# Arduinoboy_1.net
KiCad netlist of a schematic drawn in EAGLE
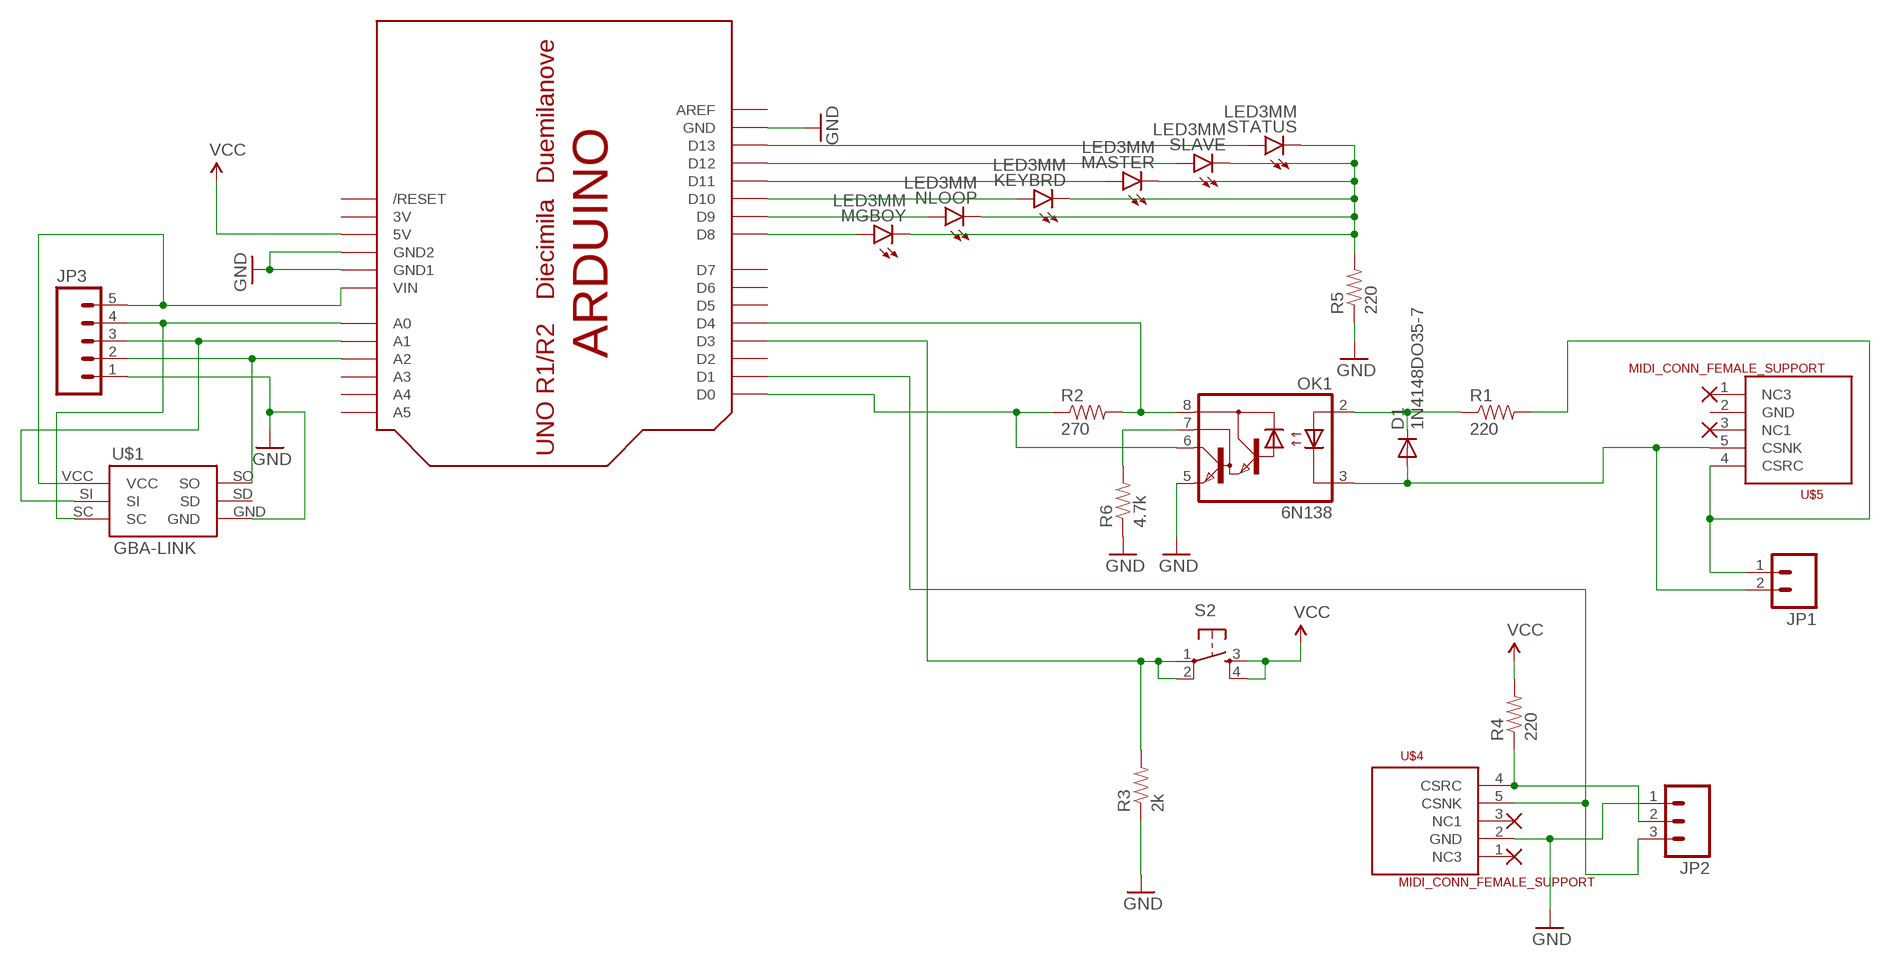
[diagram p0: schematic, sheet 1]

(export (version "E")
  (design (tool "Eeschema 10.0.6"))
  (components
    (comp (ref "D1")
      (value "1N4148DO35-7")
      (footprint "eagle-import:DO35-7")
      (libsource (lib "eagle-import") (part "1N4148DO35-7"))
    )
    (comp (ref "JP1")
      (value "M025MM")
      (footprint "eagle-import:SCREWTERMINAL-5MM-2")
      (libsource (lib "eagle-import") (part "M025MM"))
    )
    (comp (ref "JP2")
      (value "M03-SCREW-5MM")
      (footprint "eagle-import:SCREWTERMINAL-5MM-3")
      (libsource (lib "eagle-import") (part "M03-SCREW-5MM"))
    )
    (comp (ref "JP3")
      (value "M05SCREW")
      (footprint "eagle-import:SCREWTERMINAL-3.5MM-5")
      (libsource (lib "eagle-import") (part "M05SCREW"))
    )
    (comp (ref "KEYBRD")
      (value "LED3MM")
      (footprint "eagle-import:LED3MM")
      (libsource (lib "eagle-import") (part "LED3MM"))
    )
    (comp (ref "MASTER")
      (value "LED3MM")
      (footprint "eagle-import:LED3MM")
      (libsource (lib "eagle-import") (part "LED3MM"))
    )
    (comp (ref "MGBOY")
      (value "LED3MM")
      (footprint "eagle-import:LED3MM")
      (libsource (lib "eagle-import") (part "LED3MM"))
    )
    (comp (ref "NLOOP")
      (value "LED3MM")
      (footprint "eagle-import:LED3MM")
      (libsource (lib "eagle-import") (part "LED3MM"))
    )
    (comp (ref "OK1")
      (value "6N138")
      (footprint "eagle-import:DIL08")
      (libsource (lib "eagle-import") (part "6N138"))
    )
    (comp (ref "R1")
      (value "220")
      (footprint "eagle-import:AXIAL-0.3")
      (libsource (lib "eagle-import") (part "RESISTORAXIAL-0.3"))
    )
    (comp (ref "R2")
      (value "270")
      (footprint "eagle-import:AXIAL-0.3")
      (libsource (lib "eagle-import") (part "RESISTORAXIAL-0.3"))
    )
    (comp (ref "R3")
      (value "2k")
      (footprint "eagle-import:AXIAL-0.3")
      (libsource (lib "eagle-import") (part "RESISTORAXIAL-0.3"))
    )
    (comp (ref "R4")
      (value "220")
      (footprint "eagle-import:AXIAL-0.3")
      (libsource (lib "eagle-import") (part "RESISTORAXIAL-0.3"))
    )
    (comp (ref "R5")
      (value "220")
      (footprint "eagle-import:AXIAL-0.3")
      (libsource (lib "eagle-import") (part "RESISTORAXIAL-0.3"))
    )
    (comp (ref "R6")
      (value "4.7k")
      (footprint "eagle-import:AXIAL-0.3")
      (libsource (lib "eagle-import") (part "RESISTORAXIAL-0.3"))
    )
    (comp (ref "S2")
      (value "TAC_SWITCHPTH")
      (footprint "eagle-import:TACTILE-PTH")
      (libsource (lib "eagle-import") (part "TAC_SWITCHPTH"))
    )
    (comp (ref "SLAVE")
      (value "LED3MM")
      (footprint "eagle-import:LED3MM")
      (libsource (lib "eagle-import") (part "LED3MM"))
    )
    (comp (ref "STATUS")
      (value "LED3MM")
      (footprint "eagle-import:LED3MM")
      (libsource (lib "eagle-import") (part "LED3MM"))
    )
    (comp (ref "U$1")
      (value "GBA-LINK")
      (footprint "eagle-import:GBA-LINK")
      (libsource (lib "eagle-import") (part "GBA-LINK"))
    )
    (comp (ref "U$3")
      (value "ARDUINOUNO")
      (footprint "eagle-import:ARDUINO")
      (libsource (lib "eagle-import") (part "ARDUINOUNO"))
    )
    (comp (ref "U$4")
      (value "MIDI_CONN_FEMALE_SUPPORT")
      (footprint "eagle-import:DIN_5_FEMALE_SUPPORT")
      (libsource (lib "eagle-import") (part "MIDI_CONN_FEMALE_SUPPORT"))
    )
    (comp (ref "U$5")
      (value "MIDI_CONN_FEMALE_SUPPORT")
      (footprint "eagle-import:DIN_5_FEMALE_SUPPORT")
      (libsource (lib "eagle-import") (part "MIDI_CONN_FEMALE_SUPPORT"))
    )
  )
  (nets
    (net (code "1") (name "/3V") (class "Default")
      (node (ref "U$3") (pin "3V") (pinfunction "3V_3V") (pintype "power_in"))
    )
    (net (code "2") (name "GND") (class "Default")
      (node (ref "JP2") (pin "1") (pinfunction "1_1") (pintype "passive"))
      (node (ref "JP3") (pin "1") (pinfunction "1_1") (pintype "passive"))
      (node (ref "OK1") (pin "5") (pinfunction "GND_5") (pintype "passive"))
      (node (ref "R3") (pin "P$1") (pinfunction "1_P$1") (pintype "passive"))
      (node (ref "R5") (pin "P$1") (pinfunction "1_P$1") (pintype "passive"))
      (node (ref "R6") (pin "P$1") (pinfunction "1_P$1") (pintype "passive"))
      (node (ref "U$1") (pin "GND") (pinfunction "GND_GND") (pintype "bidirectional"))
      (node (ref "U$3") (pin "GND") (pinfunction "GND_GND") (pintype "power_in"))
      (node (ref "U$3") (pin "GND1") (pinfunction "GND1_GND1") (pintype "power_in"))
      (node (ref "U$3") (pin "GND2") (pinfunction "GND2_GND2") (pintype "power_in"))
      (node (ref "U$4") (pin "2") (pinfunction "GND_2") (pintype "bidirectional"))
    )
    (net (code "3") (name "Net-(JP3-Pad2)") (class "Default")
      (node (ref "JP3") (pin "2") (pinfunction "2_2") (pintype "passive"))
      (node (ref "U$1") (pin "SO") (pinfunction "SO_SO") (pintype "bidirectional"))
      (node (ref "U$3") (pin "A2") (pinfunction "A2_A2") (pintype "bidirectional"))
    )
    (net (code "4") (name "Net-(JP3-Pad3)") (class "Default")
      (node (ref "JP3") (pin "3") (pinfunction "3_3") (pintype "passive"))
      (node (ref "U$1") (pin "SI") (pinfunction "SI_SI") (pintype "bidirectional"))
      (node (ref "U$3") (pin "A1") (pinfunction "A1_A1") (pintype "bidirectional"))
    )
    (net (code "5") (name "Net-(JP3-Pad4)") (class "Default")
      (node (ref "JP3") (pin "4") (pinfunction "4_4") (pintype "passive"))
      (node (ref "U$1") (pin "SC") (pinfunction "SC_SC") (pintype "bidirectional"))
      (node (ref "U$3") (pin "A0") (pinfunction "A0_A0") (pintype "bidirectional"))
    )
    (net (code "6") (name "Net-(JP3-Pad5)") (class "Default")
      (node (ref "JP3") (pin "5") (pinfunction "5_5") (pintype "passive"))
      (node (ref "U$1") (pin "VCC") (pinfunction "VCC_VCC") (pintype "bidirectional"))
      (node (ref "U$3") (pin "VIN") (pinfunction "VIN_VIN") (pintype "power_in"))
    )
    (net (code "7") (name "Net-(KEYBRD-C)") (class "Default")
      (node (ref "KEYBRD") (pin "K") (pinfunction "C_K") (pintype "passive"))
      (node (ref "MASTER") (pin "K") (pinfunction "C_K") (pintype "passive"))
      (node (ref "MGBOY") (pin "K") (pinfunction "C_K") (pintype "passive"))
      (node (ref "NLOOP") (pin "K") (pinfunction "C_K") (pintype "passive"))
      (node (ref "R5") (pin "P$2") (pinfunction "2_P$2") (pintype "passive"))
      (node (ref "SLAVE") (pin "K") (pinfunction "C_K") (pintype "passive"))
      (node (ref "STATUS") (pin "K") (pinfunction "C_K") (pintype "passive"))
    )
    (net (code "8") (name "Net-(KEYBRD-PadA)") (class "Default")
      (node (ref "KEYBRD") (pin "A") (pinfunction "A_A") (pintype "passive"))
      (node (ref "U$3") (pin "D10") (pinfunction "D10_D10") (pintype "bidirectional"))
    )
    (net (code "9") (name "Net-(MASTER-PadA)") (class "Default")
      (node (ref "MASTER") (pin "A") (pinfunction "A_A") (pintype "passive"))
      (node (ref "U$3") (pin "D11") (pinfunction "D11_D11") (pintype "bidirectional"))
    )
    (net (code "10") (name "Net-(MGBOY-PadA)") (class "Default")
      (node (ref "MGBOY") (pin "A") (pinfunction "A_A") (pintype "passive"))
      (node (ref "U$3") (pin "D8") (pinfunction "D8_D8") (pintype "bidirectional"))
    )
    (net (code "11") (name "Net-(NLOOP-PadA)") (class "Default")
      (node (ref "NLOOP") (pin "A") (pinfunction "A_A") (pintype "passive"))
      (node (ref "U$3") (pin "D9") (pinfunction "D9_D9") (pintype "bidirectional"))
    )
    (net (code "12") (name "Net-(OK1-A)") (class "Default")
      (node (ref "D1") (pin "C") (pinfunction "C_C") (pintype "passive"))
      (node (ref "OK1") (pin "2") (pinfunction "A_2") (pintype "passive"))
      (node (ref "R1") (pin "P$1") (pinfunction "1_P$1") (pintype "passive"))
    )
    (net (code "13") (name "Net-(OK1-C)") (class "Default")
      (node (ref "D1") (pin "A") (pinfunction "A_A") (pintype "passive"))
      (node (ref "JP1") (pin "2") (pinfunction "2_2") (pintype "passive"))
      (node (ref "OK1") (pin "3") (pinfunction "C_3") (pintype "passive"))
      (node (ref "U$5") (pin "5") (pinfunction "CSNK_5") (pintype "bidirectional"))
    )
    (net (code "14") (name "Net-(OK1-VB)") (class "Default")
      (node (ref "OK1") (pin "7") (pinfunction "VB_7") (pintype "passive"))
      (node (ref "R6") (pin "P$2") (pinfunction "2_P$2") (pintype "passive"))
    )
    (net (code "15") (name "Net-(OK1-VCC)") (class "Default")
      (node (ref "OK1") (pin "8") (pinfunction "VCC_8") (pintype "passive"))
      (node (ref "R2") (pin "P$2") (pinfunction "2_P$2") (pintype "passive"))
      (node (ref "U$3") (pin "D4") (pinfunction "D4_D4") (pintype "bidirectional"))
    )
    (net (code "16") (name "Net-(OK1-VO)") (class "Default")
      (node (ref "OK1") (pin "6") (pinfunction "VO_6") (pintype "passive"))
      (node (ref "R2") (pin "P$1") (pinfunction "1_P$1") (pintype "passive"))
      (node (ref "U$3") (pin "D0") (pinfunction "D0_D0") (pintype "bidirectional"))
    )
    (net (code "17") (name "Net-(R1-2)") (class "Default")
      (node (ref "JP1") (pin "1") (pinfunction "1_1") (pintype "passive"))
      (node (ref "R1") (pin "P$2") (pinfunction "2_P$2") (pintype "passive"))
      (node (ref "U$5") (pin "4") (pinfunction "CSRC_4") (pintype "bidirectional"))
    )
    (net (code "18") (name "Net-(R3-2)") (class "Default")
      (node (ref "R3") (pin "P$2") (pinfunction "2_P$2") (pintype "passive"))
      (node (ref "S2") (pin "1") (pinfunction "1_1") (pintype "passive"))
      (node (ref "S2") (pin "2") (pinfunction "2_2") (pintype "passive"))
      (node (ref "U$3") (pin "D3") (pinfunction "D3_D3") (pintype "bidirectional"))
    )
    (net (code "19") (name "Net-(R4-1)") (class "Default")
      (node (ref "JP2") (pin "2") (pinfunction "2_2") (pintype "passive"))
      (node (ref "R4") (pin "P$1") (pinfunction "1_P$1") (pintype "passive"))
      (node (ref "U$4") (pin "4") (pinfunction "CSRC_4") (pintype "bidirectional"))
    )
    (net (code "20") (name "Net-(SLAVE-PadA)") (class "Default")
      (node (ref "SLAVE") (pin "A") (pinfunction "A_A") (pintype "passive"))
      (node (ref "U$3") (pin "D12") (pinfunction "D12_D12") (pintype "bidirectional"))
    )
    (net (code "21") (name "Net-(STATUS-PadA)") (class "Default")
      (node (ref "STATUS") (pin "A") (pinfunction "A_A") (pintype "passive"))
      (node (ref "U$3") (pin "D13") (pinfunction "D13_D13") (pintype "bidirectional"))
    )
    (net (code "22") (name "Net-(U$4-CSNK)") (class "Default")
      (node (ref "JP2") (pin "3") (pinfunction "3_3") (pintype "passive"))
      (node (ref "U$3") (pin "D1") (pinfunction "D1_D1") (pintype "bidirectional"))
      (node (ref "U$4") (pin "5") (pinfunction "CSNK_5") (pintype "bidirectional"))
    )
    (net (code "23") (name "VCC") (class "Default")
      (node (ref "R4") (pin "P$2") (pinfunction "2_P$2") (pintype "passive"))
      (node (ref "S2") (pin "3") (pinfunction "3_3") (pintype "passive"))
      (node (ref "S2") (pin "4") (pinfunction "4_4") (pintype "passive"))
      (node (ref "U$3") (pin "5V") (pinfunction "5V_5V") (pintype "power_in"))
    )
    (net (code "24") (name "unconnected-(U$1-PadSD)") (class "Default")
      (node (ref "U$1") (pin "SD") (pinfunction "SD_SD") (pintype "bidirectional"))
    )
    (net (code "25") (name "unconnected-(U$3-PadA3)") (class "Default")
      (node (ref "U$3") (pin "A3") (pinfunction "A3_A3") (pintype "bidirectional"))
    )
    (net (code "26") (name "unconnected-(U$3-PadA4)") (class "Default")
      (node (ref "U$3") (pin "A4") (pinfunction "A4_A4") (pintype "bidirectional"))
    )
    (net (code "27") (name "unconnected-(U$3-PadA5)") (class "Default")
      (node (ref "U$3") (pin "A5") (pinfunction "A5_A5") (pintype "bidirectional"))
    )
    (net (code "28") (name "unconnected-(U$3-PadAREF)") (class "Default")
      (node (ref "U$3") (pin "AREF") (pinfunction "AREF_AREF") (pintype "bidirectional"))
    )
    (net (code "29") (name "unconnected-(U$3-PadD2)") (class "Default")
      (node (ref "U$3") (pin "D2") (pinfunction "D2_D2") (pintype "bidirectional"))
    )
    (net (code "30") (name "unconnected-(U$3-PadD5)") (class "Default")
      (node (ref "U$3") (pin "D5") (pinfunction "D5_D5") (pintype "bidirectional"))
    )
    (net (code "31") (name "unconnected-(U$3-PadD6)") (class "Default")
      (node (ref "U$3") (pin "D6") (pinfunction "D6_D6") (pintype "bidirectional"))
    )
    (net (code "32") (name "unconnected-(U$3-PadD7)") (class "Default")
      (node (ref "U$3") (pin "D7") (pinfunction "D7_D7") (pintype "bidirectional"))
    )
    (net (code "33") (name "unconnected-(U$3-{slash}RESET-PadRESET)") (class "Default")
      (node (ref "U$3") (pin "RESET") (pinfunction "/RESET_RESET") (pintype "bidirectional"))
    )
    (net (code "34") (name "unconnected-(U$4-NC1-Pad3)") (class "Default")
      (node (ref "U$4") (pin "3") (pinfunction "NC1_3") (pintype "bidirectional"))
    )
    (net (code "35") (name "unconnected-(U$4-NC3-Pad1)") (class "Default")
      (node (ref "U$4") (pin "1") (pinfunction "NC3_1") (pintype "bidirectional"))
    )
    (net (code "36") (name "unconnected-(U$5-GND-Pad2)") (class "Default")
      (node (ref "U$5") (pin "2") (pinfunction "GND_2") (pintype "bidirectional"))
    )
    (net (code "37") (name "unconnected-(U$5-NC1-Pad3)") (class "Default")
      (node (ref "U$5") (pin "3") (pinfunction "NC1_3") (pintype "bidirectional"))
    )
    (net (code "38") (name "unconnected-(U$5-NC3-Pad1)") (class "Default")
      (node (ref "U$5") (pin "1") (pinfunction "NC3_1") (pintype "bidirectional"))
    )
  )
)
